# pca10040_sheet3_buttons_and_leds.net
KiCad netlist of a schematic drawn in Altium Designer
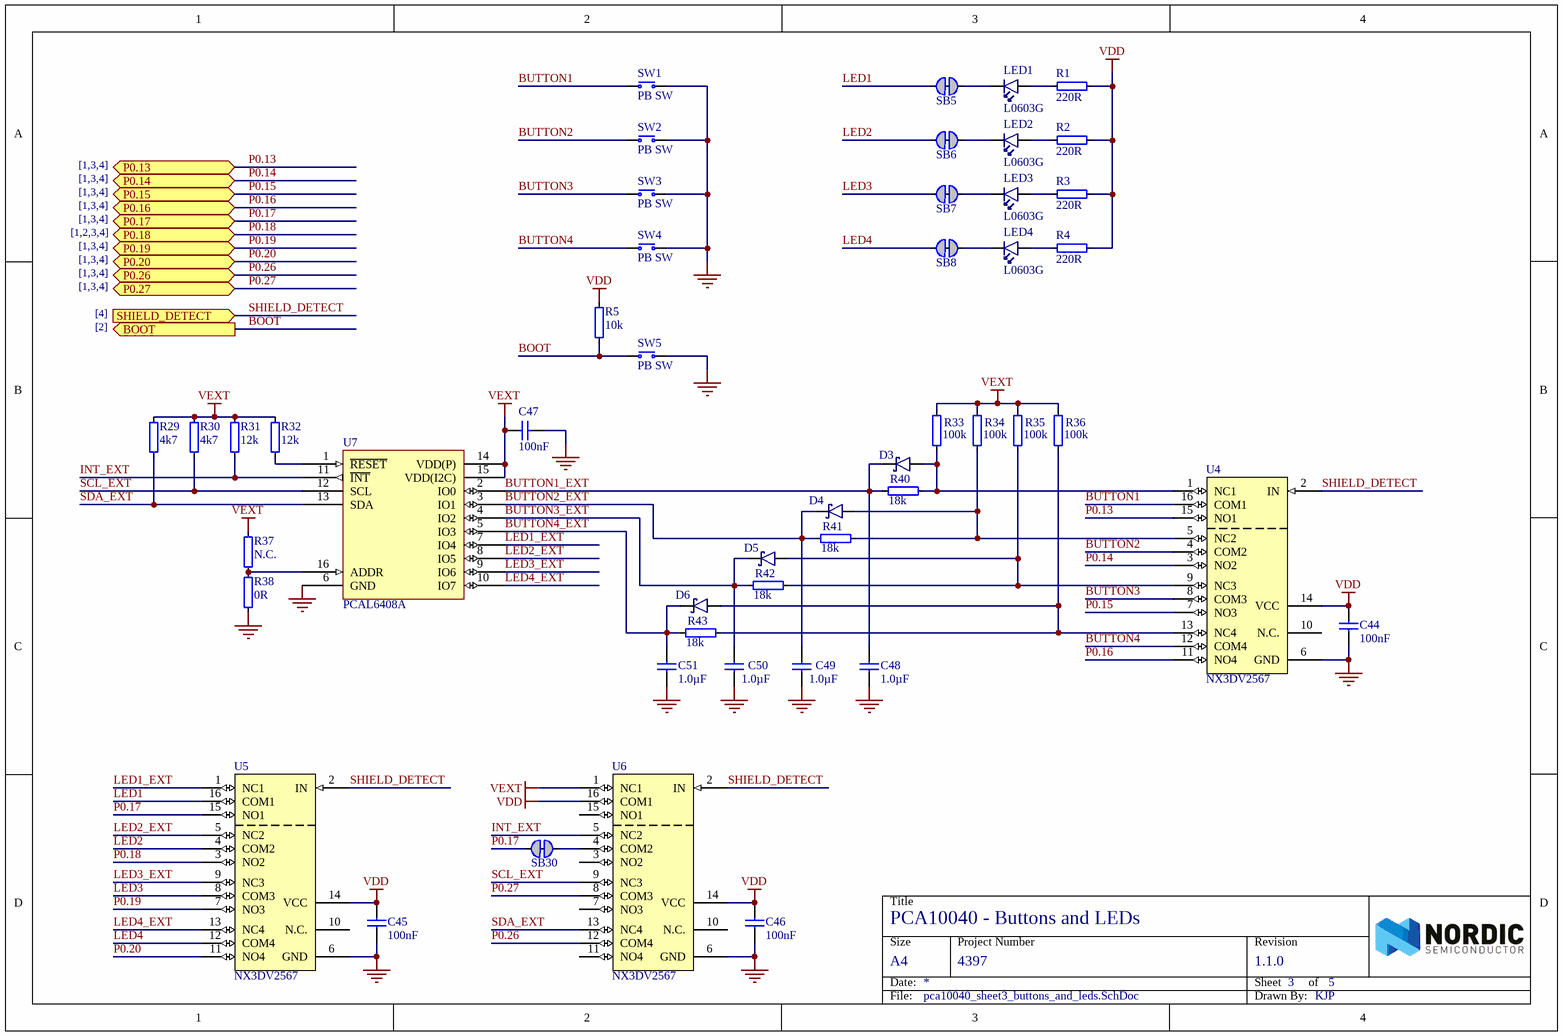
[diagram p0: pca10040_sheet3_buttons_and_leds.SchDoc]

(export (version "E")
  (design (tool "Eeschema 10.0.6"))
  (components
    (comp (ref "C44")
      (value "100nF")
      (footprint "CAPC1005X04L")
      (description "Capacitor, X7R, ±10%")
      (fields (field (name "PART NUMBER") "C0402-100n") (field (name "PUBLISHER") "Nordic Semiconductor"))
      (libsource (lib "Nordic Passive DB") (part "CAP"))
    )
    (comp (ref "C45")
      (value "100nF")
      (footprint "CAPC1005X04L")
      (description "Capacitor, X7R, ±10%")
      (fields (field (name "PART NUMBER") "C0402-100n") (field (name "PUBLISHER") "Nordic Semiconductor"))
      (libsource (lib "Nordic Passive DB") (part "CAP"))
    )
    (comp (ref "C46")
      (value "100nF")
      (footprint "CAPC1005X04L")
      (description "Capacitor, X7R, ±10%")
      (fields (field (name "PART NUMBER") "C0402-100n") (field (name "PUBLISHER") "Nordic Semiconductor"))
      (libsource (lib "Nordic Passive DB") (part "CAP"))
    )
    (comp (ref "C47")
      (value "100nF")
      (footprint "CAPC1005X04L")
      (description "Capacitor, X7R, ±10%")
      (fields (field (name "PART NUMBER") "C0402-100n") (field (name "PUBLISHER") "Nordic Semiconductor"))
      (libsource (lib "Nordic Passive DB") (part "CAP"))
    )
    (comp (ref "C48")
      (value "1.0µF")
      (footprint "CAPC1005X04L")
      (description "Capacitor, X5R, ±5%")
      (fields (field (name "PART NUMBER") "C0402-1µ0") (field (name "PUBLISHER") "Nordic Semiconductor"))
      (libsource (lib "Nordic Passive DB") (part "CAP"))
    )
    (comp (ref "C49")
      (value "1.0µF")
      (footprint "CAPC1005X04L")
      (description "Capacitor, X5R, ±5%")
      (fields (field (name "PART NUMBER") "C0402-1µ0") (field (name "PUBLISHER") "Nordic Semiconductor"))
      (libsource (lib "Nordic Passive DB") (part "CAP"))
    )
    (comp (ref "C50")
      (value "1.0µF")
      (footprint "CAPC1005X04L")
      (description "Capacitor, X5R, ±5%")
      (fields (field (name "PART NUMBER") "C0402-1µ0") (field (name "PUBLISHER") "Nordic Semiconductor"))
      (libsource (lib "Nordic Passive DB") (part "CAP"))
    )
    (comp (ref "C51")
      (value "1.0µF")
      (footprint "CAPC1005X04L")
      (description "Capacitor, X5R, ±5%")
      (fields (field (name "PART NUMBER") "C0402-1µ0") (field (name "PUBLISHER") "Nordic Semiconductor"))
      (libsource (lib "Nordic Passive DB") (part "CAP"))
    )
    (comp (ref "D3")
      (value "1PS79SB30.115")
      (footprint "SOD-523")
      (description "Diode Schottky Vf=0.38, Vr=40V, If=200mA, Ir=500nA")
      (fields (field (name "MANUFACTURER") "NXP") (field (name "PUBLISHER") "Nordic Semiconductor"))
      (libsource (lib "Nordic Discrete DB") (part "D{colon}SCHOTTKY"))
    )
    (comp (ref "D4")
      (value "1PS79SB30.115")
      (footprint "SOD-523")
      (description "Diode Schottky Vf=0.38, Vr=40V, If=200mA, Ir=500nA")
      (fields (field (name "MANUFACTURER") "NXP") (field (name "PUBLISHER") "Nordic Semiconductor"))
      (libsource (lib "Nordic Discrete DB") (part "D{colon}SCHOTTKY"))
    )
    (comp (ref "D5")
      (value "1PS79SB30.115")
      (footprint "SOD-523")
      (description "Diode Schottky Vf=0.38, Vr=40V, If=200mA, Ir=500nA")
      (fields (field (name "MANUFACTURER") "NXP") (field (name "PUBLISHER") "Nordic Semiconductor"))
      (libsource (lib "Nordic Discrete DB") (part "D{colon}SCHOTTKY"))
    )
    (comp (ref "D6")
      (value "1PS79SB30.115")
      (footprint "SOD-523")
      (description "Diode Schottky Vf=0.38, Vr=40V, If=200mA, Ir=500nA")
      (fields (field (name "MANUFACTURER") "NXP") (field (name "PUBLISHER") "Nordic Semiconductor"))
      (libsource (lib "Nordic Discrete DB") (part "D{colon}SCHOTTKY"))
    )
    (comp (ref "LED1")
      (value "L0603G")
      (footprint "LED_0603_G")
      (description "LED 0603, EL19-21SYGC")
      (fields
        (field (name "PART NUMBER") "EL19-21SYGC")
        (field (name "MANUFACTURER") "Everlight")
        (field (name "PUBLISHER") "Nordic Semiconductor")
      )
      (libsource (lib "Nordic Discrete DB") (part "D{colon}LED"))
    )
    (comp (ref "LED2")
      (value "L0603G")
      (footprint "LED_0603_G")
      (description "LED 0603, EL19-21SYGC")
      (fields
        (field (name "PART NUMBER") "EL19-21SYGC")
        (field (name "MANUFACTURER") "Everlight")
        (field (name "PUBLISHER") "Nordic Semiconductor")
      )
      (libsource (lib "Nordic Discrete DB") (part "D{colon}LED"))
    )
    (comp (ref "LED3")
      (value "L0603G")
      (footprint "LED_0603_G")
      (description "LED 0603, EL19-21SYGC")
      (fields
        (field (name "PART NUMBER") "EL19-21SYGC")
        (field (name "MANUFACTURER") "Everlight")
        (field (name "PUBLISHER") "Nordic Semiconductor")
      )
      (libsource (lib "Nordic Discrete DB") (part "D{colon}LED"))
    )
    (comp (ref "LED4")
      (value "L0603G")
      (footprint "LED_0603_G")
      (description "LED 0603, EL19-21SYGC")
      (fields
        (field (name "PART NUMBER") "EL19-21SYGC")
        (field (name "MANUFACTURER") "Everlight")
        (field (name "PUBLISHER") "Nordic Semiconductor")
      )
      (libsource (lib "Nordic Discrete DB") (part "D{colon}LED"))
    )
    (comp (ref "R1")
      (value "220R")
      (footprint "RESC1005X04L")
      (description "Resistor, ±1%, 0.063W")
      (fields (field (name "PART NUMBER") "R0402-220") (field (name "PUBLISHER") "Nordic Semiconductor"))
      (libsource (lib "Nordic Passive DB") (part "RES_1"))
    )
    (comp (ref "R2")
      (value "220R")
      (footprint "RESC1005X04L")
      (description "Resistor, ±1%, 0.063W")
      (fields (field (name "PART NUMBER") "R0402-220") (field (name "PUBLISHER") "Nordic Semiconductor"))
      (libsource (lib "Nordic Passive DB") (part "RES_1"))
    )
    (comp (ref "R3")
      (value "220R")
      (footprint "RESC1005X04L")
      (description "Resistor, ±1%, 0.063W")
      (fields (field (name "PART NUMBER") "R0402-220") (field (name "PUBLISHER") "Nordic Semiconductor"))
      (libsource (lib "Nordic Passive DB") (part "RES_1"))
    )
    (comp (ref "R4")
      (value "220R")
      (footprint "RESC1005X04L")
      (description "Resistor, ±1%, 0.063W")
      (fields (field (name "PART NUMBER") "R0402-220") (field (name "PUBLISHER") "Nordic Semiconductor"))
      (libsource (lib "Nordic Passive DB") (part "RES_1"))
    )
    (comp (ref "R5")
      (value "10k")
      (footprint "RESC1005X04L")
      (description "Resistor, ±1%, 0.063W")
      (fields (field (name "PART NUMBER") "R0402-10k") (field (name "PUBLISHER") "Nordic Semiconductor"))
      (libsource (lib "Nordic Passive DB") (part "RES_1"))
    )
    (comp (ref "R29")
      (value "4k7")
      (footprint "RESC1005X04L")
      (description "Resistor, ±1%, 0.063W")
      (fields (field (name "PART NUMBER") "R0402-4k7") (field (name "PUBLISHER") "Nordic Semiconductor"))
      (libsource (lib "Nordic Passive DB") (part "RES_1"))
    )
    (comp (ref "R30")
      (value "4k7")
      (footprint "RESC1005X04L")
      (description "Resistor, ±1%, 0.063W")
      (fields (field (name "PART NUMBER") "R0402-4k7") (field (name "PUBLISHER") "Nordic Semiconductor"))
      (libsource (lib "Nordic Passive DB") (part "RES_1"))
    )
    (comp (ref "R31")
      (value "12k")
      (footprint "RESC1005X04L")
      (description "Resistor, ±1%, 0.063W")
      (fields (field (name "PART NUMBER") "R0402-12k") (field (name "PUBLISHER") "Nordic Semiconductor"))
      (libsource (lib "Nordic Passive DB") (part "RES_1"))
    )
    (comp (ref "R32")
      (value "12k")
      (footprint "RESC1005X04L")
      (description "Resistor, ±1%, 0.063W")
      (fields (field (name "PART NUMBER") "R0402-12k") (field (name "PUBLISHER") "Nordic Semiconductor"))
      (libsource (lib "Nordic Passive DB") (part "RES_1"))
    )
    (comp (ref "R33")
      (value "100k")
      (footprint "RESC1005X04L")
      (description "Resistor, ±1%, 0.063W")
      (fields (field (name "PART NUMBER") "R0402-100k") (field (name "PUBLISHER") "Nordic Semiconductor"))
      (libsource (lib "Nordic Passive DB") (part "RES_1"))
    )
    (comp (ref "R34")
      (value "100k")
      (footprint "RESC1005X04L")
      (description "Resistor, ±1%, 0.063W")
      (fields (field (name "PART NUMBER") "R0402-100k") (field (name "PUBLISHER") "Nordic Semiconductor"))
      (libsource (lib "Nordic Passive DB") (part "RES_1"))
    )
    (comp (ref "R35")
      (value "100k")
      (footprint "RESC1005X04L")
      (description "Resistor, ±1%, 0.063W")
      (fields (field (name "PART NUMBER") "R0402-100k") (field (name "PUBLISHER") "Nordic Semiconductor"))
      (libsource (lib "Nordic Passive DB") (part "RES_1"))
    )
    (comp (ref "R36")
      (value "100k")
      (footprint "RESC1005X04L")
      (description "Resistor, ±1%, 0.063W")
      (fields (field (name "PART NUMBER") "R0402-100k") (field (name "PUBLISHER") "Nordic Semiconductor"))
      (libsource (lib "Nordic Passive DB") (part "RES_1"))
    )
    (comp (ref "R37")
      (value "N.C.")
      (footprint "RESC1005X04L")
      (description "Not mounted")
      (fields (field (name "PART NUMBER") "R0402-N.C.") (field (name "PUBLISHER") "Nordic Semiconductor"))
      (libsource (lib "Nordic Passive DB") (part "RES_1"))
    )
    (comp (ref "R38")
      (value "0R")
      (footprint "RESC1005X04L")
      (description "Resistor, ±5%, 0.063W")
      (fields (field (name "PART NUMBER") "R0402-0R") (field (name "PUBLISHER") "Nordic Semiconductor"))
      (libsource (lib "Nordic Passive DB") (part "RES_1"))
    )
    (comp (ref "R40")
      (value "18k")
      (footprint "RESC1005X04L")
      (description "Resistor, ±1%, 0.063W")
      (fields (field (name "PART NUMBER") "R0402-18k") (field (name "PUBLISHER") "Nordic Semiconductor"))
      (libsource (lib "Nordic Passive DB") (part "RES_1"))
    )
    (comp (ref "R41")
      (value "18k")
      (footprint "RESC1005X04L")
      (description "Resistor, ±1%, 0.063W")
      (fields (field (name "PART NUMBER") "R0402-18k") (field (name "PUBLISHER") "Nordic Semiconductor"))
      (libsource (lib "Nordic Passive DB") (part "RES_1"))
    )
    (comp (ref "R42")
      (value "18k")
      (footprint "RESC1005X04L")
      (description "Resistor, ±1%, 0.063W")
      (fields (field (name "PART NUMBER") "R0402-18k") (field (name "PUBLISHER") "Nordic Semiconductor"))
      (libsource (lib "Nordic Passive DB") (part "RES_1"))
    )
    (comp (ref "R43")
      (value "18k")
      (footprint "RESC1005X04L")
      (description "Resistor, ±1%, 0.063W")
      (fields (field (name "PART NUMBER") "R0402-18k") (field (name "PUBLISHER") "Nordic Semiconductor"))
      (libsource (lib "Nordic Passive DB") (part "RES_1"))
    )
    (comp (ref "SB5")
      (value "Solderbridge")
      (footprint "Solderbridge_Shorted")
      (description "Shorted Solderbridge")
      (fields
        (field (name "PART NUMBER") "Solderbridge Shorted")
        (field (name "PUBLISHER") "Nordic Semiconductor")
      )
      (libsource (lib "Nordic Passive DB") (part "SOLDERBRIDGE_SHORTED"))
    )
    (comp (ref "SB6")
      (value "Solderbridge")
      (footprint "Solderbridge_Shorted")
      (description "Shorted Solderbridge")
      (fields
        (field (name "PART NUMBER") "Solderbridge Shorted")
        (field (name "PUBLISHER") "Nordic Semiconductor")
      )
      (libsource (lib "Nordic Passive DB") (part "SOLDERBRIDGE_SHORTED"))
    )
    (comp (ref "SB7")
      (value "Solderbridge")
      (footprint "Solderbridge_Shorted")
      (description "Shorted Solderbridge")
      (fields
        (field (name "PART NUMBER") "Solderbridge Shorted")
        (field (name "PUBLISHER") "Nordic Semiconductor")
      )
      (libsource (lib "Nordic Passive DB") (part "SOLDERBRIDGE_SHORTED"))
    )
    (comp (ref "SB8")
      (value "Solderbridge")
      (footprint "Solderbridge_Shorted")
      (description "Shorted Solderbridge")
      (fields
        (field (name "PART NUMBER") "Solderbridge Shorted")
        (field (name "PUBLISHER") "Nordic Semiconductor")
      )
      (libsource (lib "Nordic Passive DB") (part "SOLDERBRIDGE_SHORTED"))
    )
    (comp (ref "SB30")
      (value "Solderbridge")
      (footprint "Solderbridge_Shorted")
      (description "Shorted Solderbridge")
      (fields
        (field (name "PART NUMBER") "Solderbridge Shorted")
        (field (name "PUBLISHER") "Nordic Semiconductor")
      )
      (libsource (lib "Nordic Passive DB") (part "SOLDERBRIDGE_SHORTED"))
    )
    (comp (ref "SW1")
      (value "PB SW")
      (footprint "ALPS_SKHUxxx010_WO_GND")
      (description "ALPS - SKHUALE010 - Tactile Switch, SPNO, SMD, 6.5x6.2x2.5mm")
      (fields
        (field (name "PART NUMBER") "ALPS_SKHUALE010")
        (field (name "MANUFACTURER") "Alps")
        (field (name "PUBLISHER") "Nordic Semiconductor")
      )
      (libsource (lib "Nordic Discrete DB") (part "SW-PB"))
    )
    (comp (ref "SW2")
      (value "PB SW")
      (footprint "ALPS_SKHUxxx010_WO_GND")
      (description "ALPS - SKHUALE010 - Tactile Switch, SPNO, SMD, 6.5x6.2x2.5mm")
      (fields
        (field (name "PART NUMBER") "ALPS_SKHUALE010")
        (field (name "MANUFACTURER") "Alps")
        (field (name "PUBLISHER") "Nordic Semiconductor")
      )
      (libsource (lib "Nordic Discrete DB") (part "SW-PB"))
    )
    (comp (ref "SW3")
      (value "PB SW")
      (footprint "ALPS_SKHUxxx010_WO_GND")
      (description "ALPS - SKHUALE010 - Tactile Switch, SPNO, SMD, 6.5x6.2x2.5mm")
      (fields
        (field (name "PART NUMBER") "ALPS_SKHUALE010")
        (field (name "MANUFACTURER") "Alps")
        (field (name "PUBLISHER") "Nordic Semiconductor")
      )
      (libsource (lib "Nordic Discrete DB") (part "SW-PB"))
    )
    (comp (ref "SW4")
      (value "PB SW")
      (footprint "ALPS_SKHUxxx010_WO_GND")
      (description "ALPS - SKHUALE010 - Tactile Switch, SPNO, SMD, 6.5x6.2x2.5mm")
      (fields
        (field (name "PART NUMBER") "ALPS_SKHUALE010")
        (field (name "MANUFACTURER") "Alps")
        (field (name "PUBLISHER") "Nordic Semiconductor")
      )
      (libsource (lib "Nordic Discrete DB") (part "SW-PB"))
    )
    (comp (ref "SW5")
      (value "PB SW")
      (footprint "ALPS_SKHUxxx010_WO_GND")
      (description "ALPS - SKHUALE010 - Tactile Switch, SPNO, SMD, 6.5x6.2x2.5mm")
      (fields
        (field (name "PART NUMBER") "ALPS_SKHUALE010")
        (field (name "MANUFACTURER") "Alps")
        (field (name "PUBLISHER") "Nordic Semiconductor")
      )
      (libsource (lib "Nordic Discrete DB") (part "SW-PB"))
    )
    (comp (ref "U4")
      (value "NX3DV2567")
      (footprint "XQFN40P180X260X50-16N")
      (description "Low-ohmic four-pole double-throw analog switch")
      (fields
        (field (name "PART NUMBER") "NX3DV2567GU")
        (field (name "MANUFACTURER") "NXP Semiconductors")
        (field (name "PUBLISHER") "Nordic Semiconductor")
      )
      (libsource (lib "Nordic Active DB") (part "NX3DV2567"))
    )
    (comp (ref "U5")
      (value "NX3DV2567")
      (footprint "XQFN40P180X260X50-16N")
      (description "Low-ohmic four-pole double-throw analog switch")
      (fields
        (field (name "PART NUMBER") "NX3DV2567GU")
        (field (name "MANUFACTURER") "NXP Semiconductors")
        (field (name "PUBLISHER") "Nordic Semiconductor")
      )
      (libsource (lib "Nordic Active DB") (part "NX3DV2567"))
    )
    (comp (ref "U6")
      (value "NX3DV2567")
      (footprint "XQFN40P180X260X50-16N")
      (description "Low-ohmic four-pole double-throw analog switch")
      (fields
        (field (name "PART NUMBER") "NX3DV2567GU")
        (field (name "MANUFACTURER") "NXP Semiconductors")
        (field (name "PUBLISHER") "Nordic Semiconductor")
      )
      (libsource (lib "Nordic Active DB") (part "NX3DV2567"))
    )
    (comp (ref "U7")
      (value "PCAL6408A")
      (footprint "XQFN40P180X260X50-16N")
      (description "8-bit I2C-bus I/O expander with interrupt output")
      (fields
        (field (name "PART NUMBER") "PCAL6408AHK")
        (field (name "MANUFACTURER") "NXP Semiconductors")
        (field (name "PUBLISHER") "Nordic Semiconductor")
      )
      (libsource (lib "Nordic Active DB") (part "PCAL6408AHK"))
    )
  )
  (nets
    (net (code "1") (name "/BOOT") (class "Default")
      (node (ref "R5") (pin "1") (pinfunction "1_1") (pintype "passive"))
      (node (ref "SW5") (pin "1") (pinfunction "N.O_1") (pintype "passive"))
    )
    (net (code "2") (name "/BUTTON1") (class "Default")
      (node (ref "SW1") (pin "1") (pinfunction "N.O_1") (pintype "passive"))
      (node (ref "U4") (pin "16") (pinfunction "COM1_16") (pintype "bidirectional"))
    )
    (net (code "3") (name "/BUTTON1_EXT") (class "Default")
      (node (ref "C48") (pin "1") (pinfunction "1_1") (pintype "passive"))
      (node (ref "D3") (pin "3") (pinfunction "C_3") (pintype "passive"))
      (node (ref "R40") (pin "1") (pinfunction "1_1") (pintype "passive"))
      (node (ref "U7") (pin "2") (pinfunction "IO0_2") (pintype "bidirectional"))
    )
    (net (code "4") (name "/BUTTON2") (class "Default")
      (node (ref "SW2") (pin "1") (pinfunction "N.O_1") (pintype "passive"))
      (node (ref "U4") (pin "4") (pinfunction "COM2_4") (pintype "bidirectional"))
    )
    (net (code "5") (name "/BUTTON2_EXT") (class "Default")
      (node (ref "C49") (pin "2") (pinfunction "2_2") (pintype "passive"))
      (node (ref "D4") (pin "3") (pinfunction "C_3") (pintype "passive"))
      (node (ref "R41") (pin "1") (pinfunction "1_1") (pintype "passive"))
      (node (ref "U7") (pin "3") (pinfunction "IO1_3") (pintype "bidirectional"))
    )
    (net (code "6") (name "/BUTTON3") (class "Default")
      (node (ref "SW3") (pin "1") (pinfunction "N.O_1") (pintype "passive"))
      (node (ref "U4") (pin "8") (pinfunction "COM3_8") (pintype "bidirectional"))
    )
    (net (code "7") (name "/BUTTON3_EXT") (class "Default")
      (node (ref "C50") (pin "2") (pinfunction "2_2") (pintype "passive"))
      (node (ref "D5") (pin "3") (pinfunction "C_3") (pintype "passive"))
      (node (ref "R42") (pin "1") (pinfunction "1_1") (pintype "passive"))
      (node (ref "U7") (pin "4") (pinfunction "IO2_4") (pintype "bidirectional"))
    )
    (net (code "8") (name "/BUTTON4") (class "Default")
      (node (ref "SW4") (pin "1") (pinfunction "N.O_1") (pintype "passive"))
      (node (ref "U4") (pin "12") (pinfunction "COM4_12") (pintype "bidirectional"))
    )
    (net (code "9") (name "/BUTTON4_EXT") (class "Default")
      (node (ref "C51") (pin "1") (pinfunction "1_1") (pintype "passive"))
      (node (ref "D6") (pin "3") (pinfunction "C_3") (pintype "passive"))
      (node (ref "R43") (pin "1") (pinfunction "1_1") (pintype "passive"))
      (node (ref "U7") (pin "5") (pinfunction "IO3_5") (pintype "bidirectional"))
    )
    (net (code "10") (name "/INT_EXT") (class "Default")
      (node (ref "R31") (pin "1") (pinfunction "1_1") (pintype "passive"))
      (node (ref "U6") (pin "5") (pinfunction "NC2_5") (pintype "bidirectional"))
      (node (ref "U7") (pin "11") (pinfunction "~{INT}_11") (pintype "output"))
    )
    (net (code "11") (name "/LED1") (class "Default")
      (node (ref "SB5") (pin "1") (pinfunction "0_1") (pintype "passive"))
      (node (ref "U5") (pin "16") (pinfunction "COM1_16") (pintype "bidirectional"))
    )
    (net (code "12") (name "/LED1_EXT") (class "Default")
      (node (ref "U5") (pin "1") (pinfunction "NC1_1") (pintype "bidirectional"))
      (node (ref "U7") (pin "7") (pinfunction "IO4_7") (pintype "bidirectional"))
    )
    (net (code "13") (name "/LED2") (class "Default")
      (node (ref "SB6") (pin "1") (pinfunction "0_1") (pintype "passive"))
      (node (ref "U5") (pin "4") (pinfunction "COM2_4") (pintype "bidirectional"))
    )
    (net (code "14") (name "/LED2_EXT") (class "Default")
      (node (ref "U5") (pin "5") (pinfunction "NC2_5") (pintype "bidirectional"))
      (node (ref "U7") (pin "8") (pinfunction "IO5_8") (pintype "bidirectional"))
    )
    (net (code "15") (name "/LED3") (class "Default")
      (node (ref "SB7") (pin "1") (pinfunction "0_1") (pintype "passive"))
      (node (ref "U5") (pin "8") (pinfunction "COM3_8") (pintype "bidirectional"))
    )
    (net (code "16") (name "/LED3_EXT") (class "Default")
      (node (ref "U5") (pin "9") (pinfunction "NC3_9") (pintype "bidirectional"))
      (node (ref "U7") (pin "9") (pinfunction "IO6_9") (pintype "bidirectional"))
    )
    (net (code "17") (name "/LED4") (class "Default")
      (node (ref "SB8") (pin "1") (pinfunction "0_1") (pintype "passive"))
      (node (ref "U5") (pin "12") (pinfunction "COM4_12") (pintype "bidirectional"))
    )
    (net (code "18") (name "/LED4_EXT") (class "Default")
      (node (ref "U5") (pin "13") (pinfunction "NC4_13") (pintype "bidirectional"))
      (node (ref "U7") (pin "10") (pinfunction "IO7_10") (pintype "bidirectional"))
    )
    (net (code "19") (name "/P0.13") (class "Default")
      (node (ref "U4") (pin "15") (pinfunction "NO1_15") (pintype "bidirectional"))
    )
    (net (code "20") (name "/P0.14") (class "Default")
      (node (ref "U4") (pin "3") (pinfunction "NO2_3") (pintype "bidirectional"))
    )
    (net (code "21") (name "/P0.15") (class "Default")
      (node (ref "U4") (pin "7") (pinfunction "NO3_7") (pintype "bidirectional"))
    )
    (net (code "22") (name "/P0.16") (class "Default")
      (node (ref "U4") (pin "11") (pinfunction "NO4_11") (pintype "bidirectional"))
    )
    (net (code "23") (name "/P0.17") (class "Default")
      (node (ref "SB30") (pin "1") (pinfunction "0_1") (pintype "passive"))
      (node (ref "U5") (pin "15") (pinfunction "NO1_15") (pintype "bidirectional"))
    )
    (net (code "24") (name "/P0.18") (class "Default")
      (node (ref "U5") (pin "3") (pinfunction "NO2_3") (pintype "bidirectional"))
    )
    (net (code "25") (name "/P0.19") (class "Default")
      (node (ref "U5") (pin "7") (pinfunction "NO3_7") (pintype "bidirectional"))
    )
    (net (code "26") (name "/P0.20") (class "Default")
      (node (ref "U5") (pin "11") (pinfunction "NO4_11") (pintype "bidirectional"))
    )
    (net (code "27") (name "/P0.26") (class "Default")
      (node (ref "U6") (pin "12") (pinfunction "COM4_12") (pintype "bidirectional"))
    )
    (net (code "28") (name "/P0.27") (class "Default")
      (node (ref "U6") (pin "8") (pinfunction "COM3_8") (pintype "bidirectional"))
    )
    (net (code "29") (name "/SCL_EXT") (class "Default")
      (node (ref "R30") (pin "1") (pinfunction "1_1") (pintype "passive"))
      (node (ref "U6") (pin "9") (pinfunction "NC3_9") (pintype "bidirectional"))
      (node (ref "U7") (pin "12") (pinfunction "SCL_12") (pintype "power_in"))
    )
    (net (code "30") (name "/SDA_EXT") (class "Default")
      (node (ref "R29") (pin "1") (pinfunction "1_1") (pintype "passive"))
      (node (ref "U6") (pin "13") (pinfunction "NC4_13") (pintype "bidirectional"))
      (node (ref "U7") (pin "13") (pinfunction "SDA_13") (pintype "passive"))
    )
    (net (code "31") (name "/SHIELD_DETECT") (class "Default")
      (node (ref "U4") (pin "2") (pinfunction "IN_2") (pintype "input"))
      (node (ref "U5") (pin "2") (pinfunction "IN_2") (pintype "input"))
      (node (ref "U6") (pin "2") (pinfunction "IN_2") (pintype "input"))
    )
    (net (code "32") (name "GND") (class "Default")
      (node (ref "C44") (pin "1") (pinfunction "1_1") (pintype "passive"))
      (node (ref "C45") (pin "1") (pinfunction "1_1") (pintype "passive"))
      (node (ref "C46") (pin "1") (pinfunction "1_1") (pintype "passive"))
      (node (ref "C47") (pin "1") (pinfunction "1_1") (pintype "passive"))
      (node (ref "C48") (pin "2") (pinfunction "2_2") (pintype "passive"))
      (node (ref "C49") (pin "1") (pinfunction "1_1") (pintype "passive"))
      (node (ref "C50") (pin "1") (pinfunction "1_1") (pintype "passive"))
      (node (ref "C51") (pin "2") (pinfunction "2_2") (pintype "passive"))
      (node (ref "R38") (pin "1") (pinfunction "1_1") (pintype "passive"))
      (node (ref "SW1") (pin "2") (pinfunction "COM_2") (pintype "passive"))
      (node (ref "SW2") (pin "2") (pinfunction "COM_2") (pintype "passive"))
      (node (ref "SW3") (pin "2") (pinfunction "COM_2") (pintype "passive"))
      (node (ref "SW4") (pin "2") (pinfunction "COM_2") (pintype "passive"))
      (node (ref "SW5") (pin "2") (pinfunction "COM_2") (pintype "passive"))
      (node (ref "U4") (pin "6") (pinfunction "GND_6") (pintype "power_in"))
      (node (ref "U5") (pin "6") (pinfunction "GND_6") (pintype "power_in"))
      (node (ref "U6") (pin "6") (pinfunction "GND_6") (pintype "power_in"))
      (node (ref "U7") (pin "6") (pinfunction "GND_6") (pintype "power_in"))
    )
    (net (code "33") (name "Net-(D3-A)") (class "Default")
      (node (ref "D3") (pin "1") (pinfunction "A_1") (pintype "passive"))
      (node (ref "R33") (pin "1") (pinfunction "1_1") (pintype "passive"))
      (node (ref "R40") (pin "2") (pinfunction "2_2") (pintype "passive"))
      (node (ref "U4") (pin "1") (pinfunction "NC1_1") (pintype "bidirectional"))
    )
    (net (code "34") (name "Net-(D4-A)") (class "Default")
      (node (ref "D4") (pin "1") (pinfunction "A_1") (pintype "passive"))
      (node (ref "R34") (pin "1") (pinfunction "1_1") (pintype "passive"))
      (node (ref "R41") (pin "2") (pinfunction "2_2") (pintype "passive"))
      (node (ref "U4") (pin "5") (pinfunction "NC2_5") (pintype "bidirectional"))
    )
    (net (code "35") (name "Net-(D5-A)") (class "Default")
      (node (ref "D5") (pin "1") (pinfunction "A_1") (pintype "passive"))
      (node (ref "R35") (pin "1") (pinfunction "1_1") (pintype "passive"))
      (node (ref "R42") (pin "2") (pinfunction "2_2") (pintype "passive"))
      (node (ref "U4") (pin "9") (pinfunction "NC3_9") (pintype "bidirectional"))
    )
    (net (code "36") (name "Net-(D6-A)") (class "Default")
      (node (ref "D6") (pin "1") (pinfunction "A_1") (pintype "passive"))
      (node (ref "R36") (pin "1") (pinfunction "1_1") (pintype "passive"))
      (node (ref "R43") (pin "2") (pinfunction "2_2") (pintype "passive"))
      (node (ref "U4") (pin "13") (pinfunction "NC4_13") (pintype "bidirectional"))
    )
    (net (code "37") (name "Net-(LED1-A)") (class "Default")
      (node (ref "LED1") (pin "2") (pinfunction "A_2") (pintype "passive"))
      (node (ref "R1") (pin "1") (pinfunction "1_1") (pintype "passive"))
    )
    (net (code "38") (name "Net-(LED1-C)") (class "Default")
      (node (ref "LED1") (pin "1") (pinfunction "C_1") (pintype "passive"))
      (node (ref "SB5") (pin "2") (pinfunction "1_2") (pintype "passive"))
    )
    (net (code "39") (name "Net-(LED2-A)") (class "Default")
      (node (ref "LED2") (pin "2") (pinfunction "A_2") (pintype "passive"))
      (node (ref "R2") (pin "1") (pinfunction "1_1") (pintype "passive"))
    )
    (net (code "40") (name "Net-(LED2-C)") (class "Default")
      (node (ref "LED2") (pin "1") (pinfunction "C_1") (pintype "passive"))
      (node (ref "SB6") (pin "2") (pinfunction "1_2") (pintype "passive"))
    )
    (net (code "41") (name "Net-(LED3-A)") (class "Default")
      (node (ref "LED3") (pin "2") (pinfunction "A_2") (pintype "passive"))
      (node (ref "R3") (pin "1") (pinfunction "1_1") (pintype "passive"))
    )
    (net (code "42") (name "Net-(LED3-C)") (class "Default")
      (node (ref "LED3") (pin "1") (pinfunction "C_1") (pintype "passive"))
      (node (ref "SB7") (pin "2") (pinfunction "1_2") (pintype "passive"))
    )
    (net (code "43") (name "Net-(LED4-A)") (class "Default")
      (node (ref "LED4") (pin "2") (pinfunction "A_2") (pintype "passive"))
      (node (ref "R4") (pin "1") (pinfunction "1_1") (pintype "passive"))
    )
    (net (code "44") (name "Net-(LED4-C)") (class "Default")
      (node (ref "LED4") (pin "1") (pinfunction "C_1") (pintype "passive"))
      (node (ref "SB8") (pin "2") (pinfunction "1_2") (pintype "passive"))
    )
    (net (code "45") (name "Net-(SB30-1)") (class "Default")
      (node (ref "SB30") (pin "2") (pinfunction "1_2") (pintype "passive"))
      (node (ref "U6") (pin "4") (pinfunction "COM2_4") (pintype "bidirectional"))
    )
    (net (code "46") (name "Net-(U7-ADDR)") (class "Default")
      (node (ref "R37") (pin "1") (pinfunction "1_1") (pintype "passive"))
      (node (ref "R38") (pin "2") (pinfunction "2_2") (pintype "passive"))
      (node (ref "U7") (pin "16") (pinfunction "ADDR_16") (pintype "input"))
    )
    (net (code "47") (name "Net-(U7-~{RESET})") (class "Default")
      (node (ref "R32") (pin "1") (pinfunction "1_1") (pintype "passive"))
      (node (ref "U7") (pin "1") (pinfunction "~{RESET}_1") (pintype "input"))
    )
    (net (code "48") (name "VDD") (class "Default")
      (node (ref "C44") (pin "2") (pinfunction "2_2") (pintype "passive"))
      (node (ref "C45") (pin "2") (pinfunction "2_2") (pintype "passive"))
      (node (ref "C46") (pin "2") (pinfunction "2_2") (pintype "passive"))
      (node (ref "R1") (pin "2") (pinfunction "2_2") (pintype "passive"))
      (node (ref "R2") (pin "2") (pinfunction "2_2") (pintype "passive"))
      (node (ref "R3") (pin "2") (pinfunction "2_2") (pintype "passive"))
      (node (ref "R4") (pin "2") (pinfunction "2_2") (pintype "passive"))
      (node (ref "R5") (pin "2") (pinfunction "2_2") (pintype "passive"))
      (node (ref "U4") (pin "14") (pinfunction "VCC_14") (pintype "power_in"))
      (node (ref "U5") (pin "14") (pinfunction "VCC_14") (pintype "power_in"))
      (node (ref "U6") (pin "14") (pinfunction "VCC_14") (pintype "power_in"))
      (node (ref "U6") (pin "16") (pinfunction "COM1_16") (pintype "bidirectional"))
    )
    (net (code "49") (name "VEXT") (class "Default")
      (node (ref "C47") (pin "2") (pinfunction "2_2") (pintype "passive"))
      (node (ref "R29") (pin "2") (pinfunction "2_2") (pintype "passive"))
      (node (ref "R30") (pin "2") (pinfunction "2_2") (pintype "passive"))
      (node (ref "R31") (pin "2") (pinfunction "2_2") (pintype "passive"))
      (node (ref "R32") (pin "2") (pinfunction "2_2") (pintype "passive"))
      (node (ref "R33") (pin "2") (pinfunction "2_2") (pintype "passive"))
      (node (ref "R34") (pin "2") (pinfunction "2_2") (pintype "passive"))
      (node (ref "R35") (pin "2") (pinfunction "2_2") (pintype "passive"))
      (node (ref "R36") (pin "2") (pinfunction "2_2") (pintype "passive"))
      (node (ref "R37") (pin "2") (pinfunction "2_2") (pintype "passive"))
      (node (ref "U6") (pin "1") (pinfunction "NC1_1") (pintype "bidirectional"))
      (node (ref "U7") (pin "14") (pinfunction "VDD(P)_14") (pintype "power_in"))
      (node (ref "U7") (pin "15") (pinfunction "VDD(I2C)_15") (pintype "power_in"))
    )
    (net (code "50") (name "unconnected-(U4-N.C.-Pad10)") (class "Default")
      (node (ref "U4") (pin "10") (pinfunction "N.C._10") (pintype "passive"))
    )
    (net (code "51") (name "unconnected-(U5-N.C.-Pad10)") (class "Default")
      (node (ref "U5") (pin "10") (pinfunction "N.C._10") (pintype "passive"))
    )
    (net (code "52") (name "unconnected-(U6-N.C.-Pad10)") (class "Default")
      (node (ref "U6") (pin "10") (pinfunction "N.C._10") (pintype "passive"))
    )
    (net (code "53") (name "unconnected-(U6-NO1-Pad15)") (class "Default")
      (node (ref "U6") (pin "15") (pinfunction "NO1_15") (pintype "bidirectional"))
    )
    (net (code "54") (name "unconnected-(U6-NO2-Pad3)") (class "Default")
      (node (ref "U6") (pin "3") (pinfunction "NO2_3") (pintype "bidirectional"))
    )
    (net (code "55") (name "unconnected-(U6-NO3-Pad7)") (class "Default")
      (node (ref "U6") (pin "7") (pinfunction "NO3_7") (pintype "bidirectional"))
    )
    (net (code "56") (name "unconnected-(U6-NO4-Pad11)") (class "Default")
      (node (ref "U6") (pin "11") (pinfunction "NO4_11") (pintype "bidirectional"))
    )
  )
)
